# MCPGrundplatte.net
KiCad netlist of a schematic drawn in EAGLE
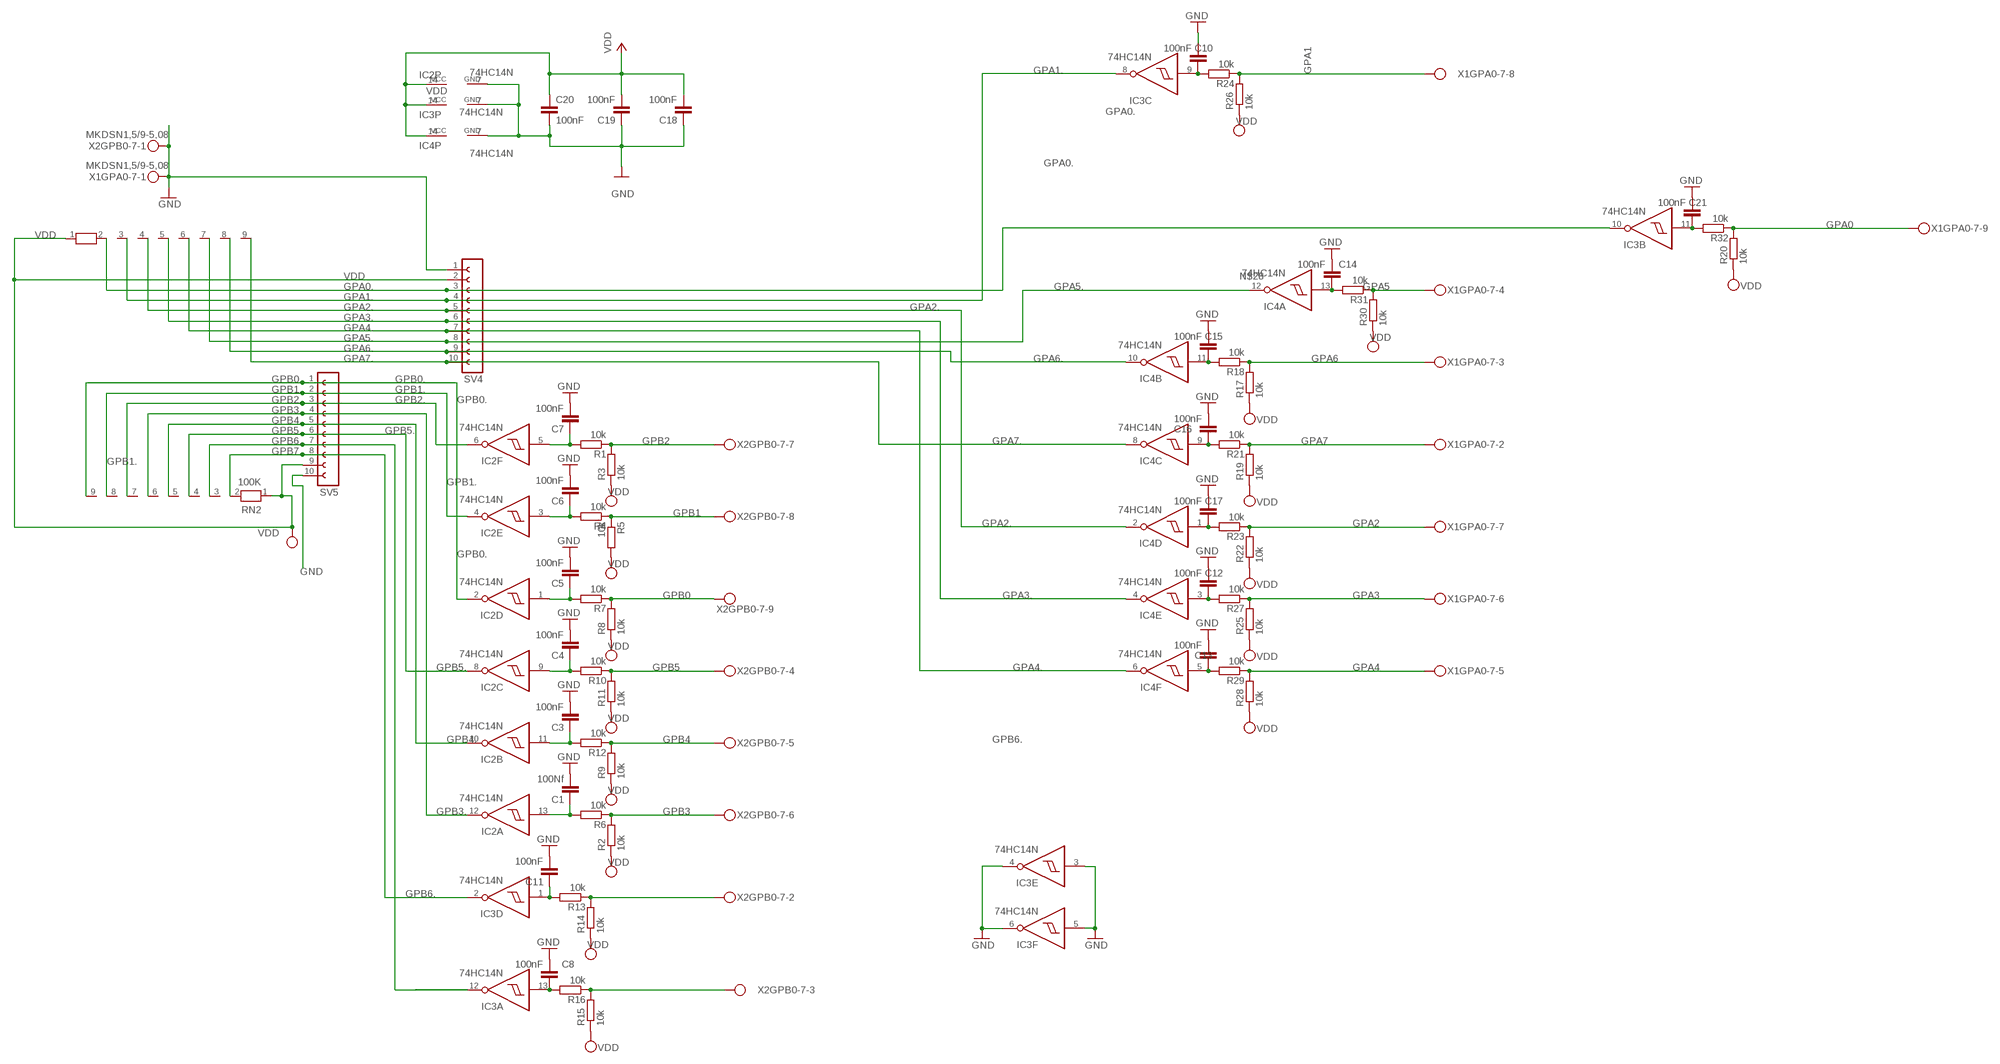
[diagram p0: schematic, sheet 1]

(export (version "E")
  (design (tool "Eeschema 10.0.6"))
  (components
    (comp (ref "C1")
      (value "100Nf")
      (footprint "eagle-import:C025-024X044")
      (libsource (lib "eagle-import") (part "C-EU025-024X044"))
    )
    (comp (ref "C3")
      (value "100nF")
      (footprint "eagle-import:C025-024X044")
      (libsource (lib "eagle-import") (part "C-EU025-024X044"))
    )
    (comp (ref "C4")
      (value "100nF")
      (footprint "eagle-import:C025-024X044")
      (libsource (lib "eagle-import") (part "C-EU025-024X044"))
    )
    (comp (ref "C5")
      (value "100nF")
      (footprint "eagle-import:C025-024X044")
      (libsource (lib "eagle-import") (part "C-EU025-024X044"))
    )
    (comp (ref "C6")
      (value "100nF")
      (footprint "eagle-import:C025-024X044")
      (libsource (lib "eagle-import") (part "C-EU025-024X044"))
    )
    (comp (ref "C7")
      (value "100nF")
      (footprint "eagle-import:C025-024X044")
      (libsource (lib "eagle-import") (part "C-EU025-024X044"))
    )
    (comp (ref "C8")
      (value "100nF")
      (footprint "eagle-import:C025-024X044")
      (libsource (lib "eagle-import") (part "C-EU025-024X044"))
    )
    (comp (ref "C10")
      (value "100nF")
      (footprint "eagle-import:C025-024X044")
      (libsource (lib "eagle-import") (part "C-EU025-024X044"))
    )
    (comp (ref "C11")
      (value "100nF")
      (footprint "eagle-import:C025-024X044")
      (libsource (lib "eagle-import") (part "C-EU025-024X044"))
    )
    (comp (ref "C12")
      (value "100nF")
      (footprint "eagle-import:C025-024X044")
      (libsource (lib "eagle-import") (part "C-EU025-024X044"))
    )
    (comp (ref "C13")
      (value "100nF")
      (footprint "eagle-import:C025-024X044")
      (libsource (lib "eagle-import") (part "C-EU025-024X044"))
    )
    (comp (ref "C14")
      (value "100nF")
      (footprint "eagle-import:C025-024X044")
      (libsource (lib "eagle-import") (part "C-EU025-024X044"))
    )
    (comp (ref "C15")
      (value "100nF")
      (footprint "eagle-import:C025-024X044")
      (libsource (lib "eagle-import") (part "C-EU025-024X044"))
    )
    (comp (ref "C16")
      (value "100nF")
      (footprint "eagle-import:C025-024X044")
      (libsource (lib "eagle-import") (part "C-EU025-024X044"))
    )
    (comp (ref "C17")
      (value "100nF")
      (footprint "eagle-import:C025-024X044")
      (libsource (lib "eagle-import") (part "C-EU025-024X044"))
    )
    (comp (ref "C18")
      (value "100nF")
      (footprint "eagle-import:C025-024X044")
      (libsource (lib "eagle-import") (part "C-EU025-024X044"))
    )
    (comp (ref "C19")
      (value "100nF")
      (footprint "eagle-import:C025-024X044")
      (libsource (lib "eagle-import") (part "C-EU025-024X044"))
    )
    (comp (ref "C20")
      (value "100nF")
      (footprint "eagle-import:C025-024X044")
      (libsource (lib "eagle-import") (part "C-EU025-024X044"))
    )
    (comp (ref "C21")
      (value "100nF")
      (footprint "eagle-import:C025-024X044")
      (libsource (lib "eagle-import") (part "C-EU025-024X044"))
    )
    (comp (ref "IC2")
      (value "74HC14N")
      (footprint "eagle-import:DIL14")
      (libsource (lib "eagle-import") (part "7414NHC"))
    )
    (comp (ref "IC3")
      (value "74HC14N")
      (footprint "eagle-import:DIL14")
      (libsource (lib "eagle-import") (part "7414NHC"))
    )
    (comp (ref "IC4")
      (value "74HC14N")
      (footprint "eagle-import:DIL14")
      (libsource (lib "eagle-import") (part "7414NHC"))
    )
    (comp (ref "R1")
      (value "10k")
      (footprint "eagle-import:0207_10")
      (libsource (lib "eagle-import") (part "R-EU_0207/10"))
    )
    (comp (ref "R2")
      (value "10k")
      (footprint "eagle-import:0207_10")
      (libsource (lib "eagle-import") (part "R-EU_0207/10"))
    )
    (comp (ref "R3")
      (value "10k")
      (footprint "eagle-import:0207_10")
      (libsource (lib "eagle-import") (part "R-EU_0207/10"))
    )
    (comp (ref "R4")
      (value "10k")
      (footprint "eagle-import:0207_10")
      (libsource (lib "eagle-import") (part "R-EU_0207/10"))
    )
    (comp (ref "R5")
      (value "10k")
      (footprint "eagle-import:0207_10")
      (libsource (lib "eagle-import") (part "R-EU_0207/10"))
    )
    (comp (ref "R6")
      (value "10k")
      (footprint "eagle-import:0207_10")
      (libsource (lib "eagle-import") (part "R-EU_0207/10"))
    )
    (comp (ref "R7")
      (value "10k")
      (footprint "eagle-import:0207_10")
      (libsource (lib "eagle-import") (part "R-EU_0207/10"))
    )
    (comp (ref "R8")
      (value "10k")
      (footprint "eagle-import:0207_10")
      (libsource (lib "eagle-import") (part "R-EU_0207/10"))
    )
    (comp (ref "R9")
      (value "10k")
      (footprint "eagle-import:0207_10")
      (libsource (lib "eagle-import") (part "R-EU_0207/10"))
    )
    (comp (ref "R10")
      (value "10k")
      (footprint "eagle-import:0207_10")
      (libsource (lib "eagle-import") (part "R-EU_0207/10"))
    )
    (comp (ref "R11")
      (value "10k")
      (footprint "eagle-import:0207_10")
      (libsource (lib "eagle-import") (part "R-EU_0207/10"))
    )
    (comp (ref "R12")
      (value "10k")
      (footprint "eagle-import:0207_10")
      (libsource (lib "eagle-import") (part "R-EU_0207/10"))
    )
    (comp (ref "R13")
      (value "10k")
      (footprint "eagle-import:0207_10")
      (libsource (lib "eagle-import") (part "R-EU_0207/10"))
    )
    (comp (ref "R14")
      (value "10k")
      (footprint "eagle-import:0207_10")
      (libsource (lib "eagle-import") (part "R-EU_0207/10"))
    )
    (comp (ref "R15")
      (value "10k")
      (footprint "eagle-import:0207_10")
      (libsource (lib "eagle-import") (part "R-EU_0207/10"))
    )
    (comp (ref "R16")
      (value "10k")
      (footprint "eagle-import:0207_10")
      (libsource (lib "eagle-import") (part "R-EU_0207/10"))
    )
    (comp (ref "R17")
      (value "10k")
      (footprint "eagle-import:0207_10")
      (libsource (lib "eagle-import") (part "R-EU_0207/10"))
    )
    (comp (ref "R18")
      (value "10k")
      (footprint "eagle-import:0207_10")
      (libsource (lib "eagle-import") (part "R-EU_0207/10"))
    )
    (comp (ref "R19")
      (value "10k")
      (footprint "eagle-import:0207_10")
      (libsource (lib "eagle-import") (part "R-EU_0207/10"))
    )
    (comp (ref "R20")
      (value "10k")
      (footprint "eagle-import:0207_10")
      (libsource (lib "eagle-import") (part "R-EU_0207/10"))
    )
    (comp (ref "R21")
      (value "10k")
      (footprint "eagle-import:0207_10")
      (libsource (lib "eagle-import") (part "R-EU_0207/10"))
    )
    (comp (ref "R22")
      (value "10k")
      (footprint "eagle-import:0207_10")
      (libsource (lib "eagle-import") (part "R-EU_0207/10"))
    )
    (comp (ref "R23")
      (value "10k")
      (footprint "eagle-import:0207_10")
      (libsource (lib "eagle-import") (part "R-EU_0207/10"))
    )
    (comp (ref "R24")
      (value "10k")
      (footprint "eagle-import:0207_10")
      (libsource (lib "eagle-import") (part "R-EU_0207/10"))
    )
    (comp (ref "R25")
      (value "10k")
      (footprint "eagle-import:0207_10")
      (libsource (lib "eagle-import") (part "R-EU_0207/10"))
    )
    (comp (ref "R26")
      (value "10k")
      (footprint "eagle-import:0207_10")
      (libsource (lib "eagle-import") (part "R-EU_0207/10"))
    )
    (comp (ref "R27")
      (value "10k")
      (footprint "eagle-import:0207_10")
      (libsource (lib "eagle-import") (part "R-EU_0207/10"))
    )
    (comp (ref "R28")
      (value "10k")
      (footprint "eagle-import:0207_10")
      (libsource (lib "eagle-import") (part "R-EU_0207/10"))
    )
    (comp (ref "R29")
      (value "10k")
      (footprint "eagle-import:0207_10")
      (libsource (lib "eagle-import") (part "R-EU_0207/10"))
    )
    (comp (ref "R30")
      (value "10k")
      (footprint "eagle-import:0207_10")
      (libsource (lib "eagle-import") (part "R-EU_0207/10"))
    )
    (comp (ref "R31")
      (value "10k")
      (footprint "eagle-import:0207_10")
      (libsource (lib "eagle-import") (part "R-EU_0207/10"))
    )
    (comp (ref "R32")
      (value "10k")
      (footprint "eagle-import:0207_10")
      (libsource (lib "eagle-import") (part "R-EU_0207/10"))
    )
    (comp (ref "RN1")
      (value "100K")
      (footprint "eagle-import:RN-9")
      (fields (field (name "SPICEPREFIX") "X"))
      (libsource (lib "eagle-import") (part "RN08"))
    )
    (comp (ref "RN2")
      (value "100K")
      (footprint "eagle-import:RN-9")
      (libsource (lib "eagle-import") (part "RN08"))
    )
    (comp (ref "SV4")
      (value "FE10-1")
      (footprint "eagle-import:FE10")
      (libsource (lib "eagle-import") (part "FE10-1"))
    )
    (comp (ref "SV5")
      (value "FE10-1")
      (footprint "eagle-import:FE10")
      (libsource (lib "eagle-import") (part "FE10-1"))
    )
    (comp (ref "X1GPA0-7")
      (value "MKDSN1,5/9-5,08")
      (footprint "eagle-import:MKDSN1,5_9-5,08")
      (libsource (lib "eagle-import") (part "MKDSN1,5/9-5,08"))
    )
    (comp (ref "X2GPB0-7")
      (value "MKDSN1,5/9-5,08")
      (footprint "eagle-import:MKDSN1,5_9-5,08")
      (libsource (lib "eagle-import") (part "MKDSN1,5/9-5,08"))
    )
  )
  (nets
    (net (code "1") (name "/GPA0") (class "Default")
      (node (ref "R20") (pin "2") (pinfunction "2_2") (pintype "passive"))
      (node (ref "R32") (pin "1") (pinfunction "1_1") (pintype "passive"))
      (node (ref "X1GPA0-7") (pin "9") (pinfunction "KL_9") (pintype "passive"))
    )
    (net (code "2") (name "/GPA0.") (class "Default")
      (node (ref "IC3") (pin "10") (pinfunction "O_10") (pintype "output"))
      (node (ref "RN1") (pin "2") (pinfunction "2_2") (pintype "passive"))
      (node (ref "SV4") (pin "3") (pinfunction "3_3") (pintype "passive"))
    )
    (net (code "3") (name "/GPA1") (class "Default")
      (node (ref "R24") (pin "1") (pinfunction "1_1") (pintype "passive"))
      (node (ref "R26") (pin "2") (pinfunction "2_2") (pintype "passive"))
      (node (ref "X1GPA0-7") (pin "8") (pinfunction "KL_8") (pintype "passive"))
    )
    (net (code "4") (name "/GPA1.") (class "Default")
      (node (ref "IC3") (pin "8") (pinfunction "O_8") (pintype "output"))
      (node (ref "RN1") (pin "3") (pinfunction "3_3") (pintype "passive"))
      (node (ref "SV4") (pin "4") (pinfunction "4_4") (pintype "passive"))
    )
    (net (code "5") (name "/GPA2") (class "Default")
      (node (ref "R22") (pin "2") (pinfunction "2_2") (pintype "passive"))
      (node (ref "R23") (pin "1") (pinfunction "1_1") (pintype "passive"))
      (node (ref "X1GPA0-7") (pin "7") (pinfunction "KL_7") (pintype "passive"))
    )
    (net (code "6") (name "/GPA2.") (class "Default")
      (node (ref "IC4") (pin "2") (pinfunction "O_2") (pintype "output"))
      (node (ref "RN1") (pin "4") (pinfunction "4_4") (pintype "passive"))
      (node (ref "SV4") (pin "5") (pinfunction "5_5") (pintype "passive"))
    )
    (net (code "7") (name "/GPA3") (class "Default")
      (node (ref "R25") (pin "2") (pinfunction "2_2") (pintype "passive"))
      (node (ref "R27") (pin "1") (pinfunction "1_1") (pintype "passive"))
      (node (ref "X1GPA0-7") (pin "6") (pinfunction "KL_6") (pintype "passive"))
    )
    (net (code "8") (name "/GPA3.") (class "Default")
      (node (ref "IC4") (pin "4") (pinfunction "O_4") (pintype "output"))
      (node (ref "RN1") (pin "5") (pinfunction "5_5") (pintype "passive"))
      (node (ref "SV4") (pin "6") (pinfunction "6_6") (pintype "passive"))
    )
    (net (code "9") (name "/GPA4") (class "Default")
      (node (ref "R28") (pin "2") (pinfunction "2_2") (pintype "passive"))
      (node (ref "R29") (pin "1") (pinfunction "1_1") (pintype "passive"))
      (node (ref "X1GPA0-7") (pin "5") (pinfunction "KL_5") (pintype "passive"))
    )
    (net (code "10") (name "/GPA4.") (class "Default")
      (node (ref "IC4") (pin "6") (pinfunction "O_6") (pintype "output"))
      (node (ref "RN1") (pin "6") (pinfunction "6_6") (pintype "passive"))
      (node (ref "SV4") (pin "7") (pinfunction "7_7") (pintype "passive"))
    )
    (net (code "11") (name "/GPA5") (class "Default")
      (node (ref "R30") (pin "2") (pinfunction "2_2") (pintype "passive"))
      (node (ref "R31") (pin "1") (pinfunction "1_1") (pintype "passive"))
      (node (ref "X1GPA0-7") (pin "4") (pinfunction "KL_4") (pintype "passive"))
    )
    (net (code "12") (name "/GPA5.") (class "Default")
      (node (ref "IC4") (pin "12") (pinfunction "O_12") (pintype "output"))
      (node (ref "RN1") (pin "7") (pinfunction "7_7") (pintype "passive"))
      (node (ref "SV4") (pin "8") (pinfunction "8_8") (pintype "passive"))
    )
    (net (code "13") (name "/GPA6") (class "Default")
      (node (ref "R17") (pin "2") (pinfunction "2_2") (pintype "passive"))
      (node (ref "R18") (pin "1") (pinfunction "1_1") (pintype "passive"))
      (node (ref "X1GPA0-7") (pin "3") (pinfunction "KL_3") (pintype "passive"))
    )
    (net (code "14") (name "/GPA6.") (class "Default")
      (node (ref "IC4") (pin "10") (pinfunction "O_10") (pintype "output"))
      (node (ref "RN1") (pin "8") (pinfunction "8_8") (pintype "passive"))
      (node (ref "SV4") (pin "9") (pinfunction "9_9") (pintype "passive"))
    )
    (net (code "15") (name "/GPA7") (class "Default")
      (node (ref "R19") (pin "2") (pinfunction "2_2") (pintype "passive"))
      (node (ref "R21") (pin "1") (pinfunction "1_1") (pintype "passive"))
      (node (ref "X1GPA0-7") (pin "2") (pinfunction "KL_2") (pintype "passive"))
    )
    (net (code "16") (name "/GPA7.") (class "Default")
      (node (ref "IC4") (pin "8") (pinfunction "O_8") (pintype "output"))
      (node (ref "RN1") (pin "9") (pinfunction "9_9") (pintype "passive"))
      (node (ref "SV4") (pin "10") (pinfunction "10_10") (pintype "passive"))
    )
    (net (code "17") (name "/GPB0") (class "Default")
      (node (ref "R7") (pin "1") (pinfunction "1_1") (pintype "passive"))
      (node (ref "R8") (pin "2") (pinfunction "2_2") (pintype "passive"))
      (node (ref "X2GPB0-7") (pin "9") (pinfunction "KL_9") (pintype "passive"))
    )
    (net (code "18") (name "/GPB0.") (class "Default")
      (node (ref "IC2") (pin "2") (pinfunction "O_2") (pintype "output"))
      (node (ref "RN2") (pin "9") (pinfunction "9_9") (pintype "passive"))
      (node (ref "SV5") (pin "1") (pinfunction "1_1") (pintype "passive"))
    )
    (net (code "19") (name "/GPB1") (class "Default")
      (node (ref "R4") (pin "1") (pinfunction "1_1") (pintype "passive"))
      (node (ref "R5") (pin "1") (pinfunction "1_1") (pintype "passive"))
      (node (ref "X2GPB0-7") (pin "8") (pinfunction "KL_8") (pintype "passive"))
    )
    (net (code "20") (name "/GPB1.") (class "Default")
      (node (ref "IC2") (pin "4") (pinfunction "O_4") (pintype "output"))
      (node (ref "RN2") (pin "8") (pinfunction "8_8") (pintype "passive"))
      (node (ref "SV5") (pin "2") (pinfunction "2_2") (pintype "passive"))
    )
    (net (code "21") (name "/GPB2") (class "Default")
      (node (ref "R1") (pin "1") (pinfunction "1_1") (pintype "passive"))
      (node (ref "R3") (pin "2") (pinfunction "2_2") (pintype "passive"))
      (node (ref "X2GPB0-7") (pin "7") (pinfunction "KL_7") (pintype "passive"))
    )
    (net (code "22") (name "/GPB2.") (class "Default")
      (node (ref "IC2") (pin "6") (pinfunction "O_6") (pintype "output"))
      (node (ref "RN2") (pin "7") (pinfunction "7_7") (pintype "passive"))
      (node (ref "SV5") (pin "3") (pinfunction "3_3") (pintype "passive"))
    )
    (net (code "23") (name "/GPB3") (class "Default")
      (node (ref "R2") (pin "2") (pinfunction "2_2") (pintype "passive"))
      (node (ref "R6") (pin "1") (pinfunction "1_1") (pintype "passive"))
      (node (ref "X2GPB0-7") (pin "6") (pinfunction "KL_6") (pintype "passive"))
    )
    (net (code "24") (name "/GPB3.") (class "Default")
      (node (ref "IC2") (pin "12") (pinfunction "O_12") (pintype "output"))
      (node (ref "RN2") (pin "6") (pinfunction "6_6") (pintype "passive"))
      (node (ref "SV5") (pin "4") (pinfunction "4_4") (pintype "passive"))
    )
    (net (code "25") (name "/GPB4") (class "Default")
      (node (ref "R12") (pin "1") (pinfunction "1_1") (pintype "passive"))
      (node (ref "R9") (pin "2") (pinfunction "2_2") (pintype "passive"))
      (node (ref "X2GPB0-7") (pin "5") (pinfunction "KL_5") (pintype "passive"))
    )
    (net (code "26") (name "/GPB4.") (class "Default")
      (node (ref "IC2") (pin "10") (pinfunction "O_10") (pintype "output"))
      (node (ref "RN2") (pin "5") (pinfunction "5_5") (pintype "passive"))
      (node (ref "SV5") (pin "5") (pinfunction "5_5") (pintype "passive"))
    )
    (net (code "27") (name "/GPB5") (class "Default")
      (node (ref "R10") (pin "1") (pinfunction "1_1") (pintype "passive"))
      (node (ref "R11") (pin "2") (pinfunction "2_2") (pintype "passive"))
      (node (ref "X2GPB0-7") (pin "4") (pinfunction "KL_4") (pintype "passive"))
    )
    (net (code "28") (name "/GPB5.") (class "Default")
      (node (ref "IC2") (pin "8") (pinfunction "O_8") (pintype "output"))
      (node (ref "RN2") (pin "4") (pinfunction "4_4") (pintype "passive"))
      (node (ref "SV5") (pin "6") (pinfunction "6_6") (pintype "passive"))
    )
    (net (code "29") (name "/GPB6.") (class "Default")
      (node (ref "IC3") (pin "12") (pinfunction "O_12") (pintype "output"))
      (node (ref "RN2") (pin "3") (pinfunction "3_3") (pintype "passive"))
      (node (ref "SV5") (pin "7") (pinfunction "7_7") (pintype "passive"))
    )
    (net (code "30") (name "/GPB7.") (class "Default")
      (node (ref "IC3") (pin "2") (pinfunction "O_2") (pintype "output"))
      (node (ref "RN2") (pin "2") (pinfunction "2_2") (pintype "passive"))
      (node (ref "SV5") (pin "8") (pinfunction "8_8") (pintype "passive"))
    )
    (net (code "32") (name "GND") (class "Default")
      (node (ref "C1") (pin "2") (pinfunction "2_2") (pintype "passive"))
      (node (ref "C10") (pin "2") (pinfunction "2_2") (pintype "passive"))
      (node (ref "C11") (pin "2") (pinfunction "2_2") (pintype "passive"))
      (node (ref "C12") (pin "2") (pinfunction "2_2") (pintype "passive"))
      (node (ref "C13") (pin "2") (pinfunction "2_2") (pintype "passive"))
      (node (ref "C14") (pin "2") (pinfunction "2_2") (pintype "passive"))
      (node (ref "C15") (pin "2") (pinfunction "2_2") (pintype "passive"))
      (node (ref "C16") (pin "2") (pinfunction "2_2") (pintype "passive"))
      (node (ref "C17") (pin "2") (pinfunction "2_2") (pintype "passive"))
      (node (ref "C18") (pin "1") (pinfunction "1_1") (pintype "passive"))
      (node (ref "C19") (pin "1") (pinfunction "1_1") (pintype "passive"))
      (node (ref "C20") (pin "2") (pinfunction "2_2") (pintype "passive"))
      (node (ref "C21") (pin "2") (pinfunction "2_2") (pintype "passive"))
      (node (ref "C3") (pin "2") (pinfunction "2_2") (pintype "passive"))
      (node (ref "C4") (pin "2") (pinfunction "2_2") (pintype "passive"))
      (node (ref "C5") (pin "2") (pinfunction "2_2") (pintype "passive"))
      (node (ref "C6") (pin "2") (pinfunction "2_2") (pintype "passive"))
      (node (ref "C7") (pin "2") (pinfunction "2_2") (pintype "passive"))
      (node (ref "C8") (pin "2") (pinfunction "2_2") (pintype "passive"))
      (node (ref "IC2") (pin "7") (pinfunction "GND_7") (pintype "power_in"))
      (node (ref "IC3") (pin "3") (pinfunction "I_3") (pintype "input"))
      (node (ref "IC3") (pin "4") (pinfunction "O_4") (pintype "output"))
      (node (ref "IC3") (pin "5") (pinfunction "I_5") (pintype "input"))
      (node (ref "IC3") (pin "6") (pinfunction "O_6") (pintype "output"))
      (node (ref "IC3") (pin "7") (pinfunction "GND_7") (pintype "power_in"))
      (node (ref "IC4") (pin "7") (pinfunction "GND_7") (pintype "power_in"))
      (node (ref "SV4") (pin "1") (pinfunction "1_1") (pintype "passive"))
      (node (ref "SV5") (pin "10") (pinfunction "10_10") (pintype "passive"))
      (node (ref "X1GPA0-7") (pin "1") (pinfunction "KL_1") (pintype "passive"))
      (node (ref "X2GPB0-7") (pin "1") (pinfunction "KL_1") (pintype "passive"))
    )
    (net (code "33") (name "Net-(IC2A-I)") (class "Default")
      (node (ref "C1") (pin "1") (pinfunction "1_1") (pintype "passive"))
      (node (ref "IC2") (pin "13") (pinfunction "I_13") (pintype "input"))
      (node (ref "R6") (pin "2") (pinfunction "2_2") (pintype "passive"))
    )
    (net (code "34") (name "Net-(IC2B-I)") (class "Default")
      (node (ref "C3") (pin "1") (pinfunction "1_1") (pintype "passive"))
      (node (ref "IC2") (pin "11") (pinfunction "I_11") (pintype "input"))
      (node (ref "R12") (pin "2") (pinfunction "2_2") (pintype "passive"))
    )
    (net (code "35") (name "Net-(IC2C-I)") (class "Default")
      (node (ref "C4") (pin "1") (pinfunction "1_1") (pintype "passive"))
      (node (ref "IC2") (pin "9") (pinfunction "I_9") (pintype "input"))
      (node (ref "R10") (pin "2") (pinfunction "2_2") (pintype "passive"))
    )
    (net (code "36") (name "Net-(IC2D-I)") (class "Default")
      (node (ref "C5") (pin "1") (pinfunction "1_1") (pintype "passive"))
      (node (ref "IC2") (pin "1") (pinfunction "I_1") (pintype "input"))
      (node (ref "R7") (pin "2") (pinfunction "2_2") (pintype "passive"))
    )
    (net (code "37") (name "Net-(IC2E-I)") (class "Default")
      (node (ref "C6") (pin "1") (pinfunction "1_1") (pintype "passive"))
      (node (ref "IC2") (pin "3") (pinfunction "I_3") (pintype "input"))
      (node (ref "R4") (pin "2") (pinfunction "2_2") (pintype "passive"))
    )
    (net (code "38") (name "Net-(IC2F-I)") (class "Default")
      (node (ref "C7") (pin "1") (pinfunction "1_1") (pintype "passive"))
      (node (ref "IC2") (pin "5") (pinfunction "I_5") (pintype "input"))
      (node (ref "R1") (pin "2") (pinfunction "2_2") (pintype "passive"))
    )
    (net (code "39") (name "Net-(IC3A-I)") (class "Default")
      (node (ref "C8") (pin "1") (pinfunction "1_1") (pintype "passive"))
      (node (ref "IC3") (pin "13") (pinfunction "I_13") (pintype "input"))
      (node (ref "R16") (pin "2") (pinfunction "2_2") (pintype "passive"))
    )
    (net (code "40") (name "Net-(IC3B-I)") (class "Default")
      (node (ref "C21") (pin "1") (pinfunction "1_1") (pintype "passive"))
      (node (ref "IC3") (pin "11") (pinfunction "I_11") (pintype "input"))
      (node (ref "R32") (pin "2") (pinfunction "2_2") (pintype "passive"))
    )
    (net (code "41") (name "Net-(IC3C-I)") (class "Default")
      (node (ref "C10") (pin "1") (pinfunction "1_1") (pintype "passive"))
      (node (ref "IC3") (pin "9") (pinfunction "I_9") (pintype "input"))
      (node (ref "R24") (pin "2") (pinfunction "2_2") (pintype "passive"))
    )
    (net (code "42") (name "Net-(IC3D-I)") (class "Default")
      (node (ref "C11") (pin "1") (pinfunction "1_1") (pintype "passive"))
      (node (ref "IC3") (pin "1") (pinfunction "I_1") (pintype "input"))
      (node (ref "R13") (pin "2") (pinfunction "2_2") (pintype "passive"))
    )
    (net (code "43") (name "Net-(IC4A-I)") (class "Default")
      (node (ref "C14") (pin "1") (pinfunction "1_1") (pintype "passive"))
      (node (ref "IC4") (pin "13") (pinfunction "I_13") (pintype "input"))
      (node (ref "R31") (pin "2") (pinfunction "2_2") (pintype "passive"))
    )
    (net (code "44") (name "Net-(IC4B-I)") (class "Default")
      (node (ref "C15") (pin "1") (pinfunction "1_1") (pintype "passive"))
      (node (ref "IC4") (pin "11") (pinfunction "I_11") (pintype "input"))
      (node (ref "R18") (pin "2") (pinfunction "2_2") (pintype "passive"))
    )
    (net (code "45") (name "Net-(IC4C-I)") (class "Default")
      (node (ref "C16") (pin "1") (pinfunction "1_1") (pintype "passive"))
      (node (ref "IC4") (pin "9") (pinfunction "I_9") (pintype "input"))
      (node (ref "R21") (pin "2") (pinfunction "2_2") (pintype "passive"))
    )
    (net (code "46") (name "Net-(IC4D-I)") (class "Default")
      (node (ref "C17") (pin "1") (pinfunction "1_1") (pintype "passive"))
      (node (ref "IC4") (pin "1") (pinfunction "I_1") (pintype "input"))
      (node (ref "R23") (pin "2") (pinfunction "2_2") (pintype "passive"))
    )
    (net (code "47") (name "Net-(IC4E-I)") (class "Default")
      (node (ref "C12") (pin "1") (pinfunction "1_1") (pintype "passive"))
      (node (ref "IC4") (pin "3") (pinfunction "I_3") (pintype "input"))
      (node (ref "R27") (pin "2") (pinfunction "2_2") (pintype "passive"))
    )
    (net (code "48") (name "Net-(IC4F-I)") (class "Default")
      (node (ref "C13") (pin "1") (pinfunction "1_1") (pintype "passive"))
      (node (ref "IC4") (pin "5") (pinfunction "I_5") (pintype "input"))
      (node (ref "R29") (pin "2") (pinfunction "2_2") (pintype "passive"))
    )
    (net (code "49") (name "Net-(X2GPB0-7B-KL)") (class "Default")
      (node (ref "R13") (pin "1") (pinfunction "1_1") (pintype "passive"))
      (node (ref "R14") (pin "2") (pinfunction "2_2") (pintype "passive"))
      (node (ref "X2GPB0-7") (pin "2") (pinfunction "KL_2") (pintype "passive"))
    )
    (net (code "50") (name "Net-(X2GPB0-7C-KL)") (class "Default")
      (node (ref "R15") (pin "2") (pinfunction "2_2") (pintype "passive"))
      (node (ref "R16") (pin "1") (pinfunction "1_1") (pintype "passive"))
      (node (ref "X2GPB0-7") (pin "3") (pinfunction "KL_3") (pintype "passive"))
    )
    (net (code "51") (name "VDD") (class "Default")
      (node (ref "C18") (pin "2") (pinfunction "2_2") (pintype "passive"))
      (node (ref "C19") (pin "2") (pinfunction "2_2") (pintype "passive"))
      (node (ref "C20") (pin "1") (pinfunction "1_1") (pintype "passive"))
      (node (ref "IC2") (pin "14") (pinfunction "VCC_14") (pintype "power_in"))
      (node (ref "IC3") (pin "14") (pinfunction "VCC_14") (pintype "power_in"))
      (node (ref "IC4") (pin "14") (pinfunction "VCC_14") (pintype "power_in"))
      (node (ref "R11") (pin "1") (pinfunction "1_1") (pintype "passive"))
      (node (ref "R14") (pin "1") (pinfunction "1_1") (pintype "passive"))
      (node (ref "R15") (pin "1") (pinfunction "1_1") (pintype "passive"))
      (node (ref "R17") (pin "1") (pinfunction "1_1") (pintype "passive"))
      (node (ref "R19") (pin "1") (pinfunction "1_1") (pintype "passive"))
      (node (ref "R2") (pin "1") (pinfunction "1_1") (pintype "passive"))
      (node (ref "R20") (pin "1") (pinfunction "1_1") (pintype "passive"))
      (node (ref "R22") (pin "1") (pinfunction "1_1") (pintype "passive"))
      (node (ref "R25") (pin "1") (pinfunction "1_1") (pintype "passive"))
      (node (ref "R26") (pin "1") (pinfunction "1_1") (pintype "passive"))
      (node (ref "R28") (pin "1") (pinfunction "1_1") (pintype "passive"))
      (node (ref "R3") (pin "1") (pinfunction "1_1") (pintype "passive"))
      (node (ref "R30") (pin "1") (pinfunction "1_1") (pintype "passive"))
      (node (ref "R5") (pin "2") (pinfunction "2_2") (pintype "passive"))
      (node (ref "R8") (pin "1") (pinfunction "1_1") (pintype "passive"))
      (node (ref "R9") (pin "1") (pinfunction "1_1") (pintype "passive"))
      (node (ref "RN1") (pin "1") (pinfunction "1_1") (pintype "passive"))
      (node (ref "RN2") (pin "1") (pinfunction "1_1") (pintype "passive"))
      (node (ref "SV4") (pin "2") (pinfunction "2_2") (pintype "passive"))
      (node (ref "SV5") (pin "9") (pinfunction "9_9") (pintype "passive"))
    )
  )
)
